# polarshield3_0.net
KiCad netlist of a schematic drawn in EAGLE
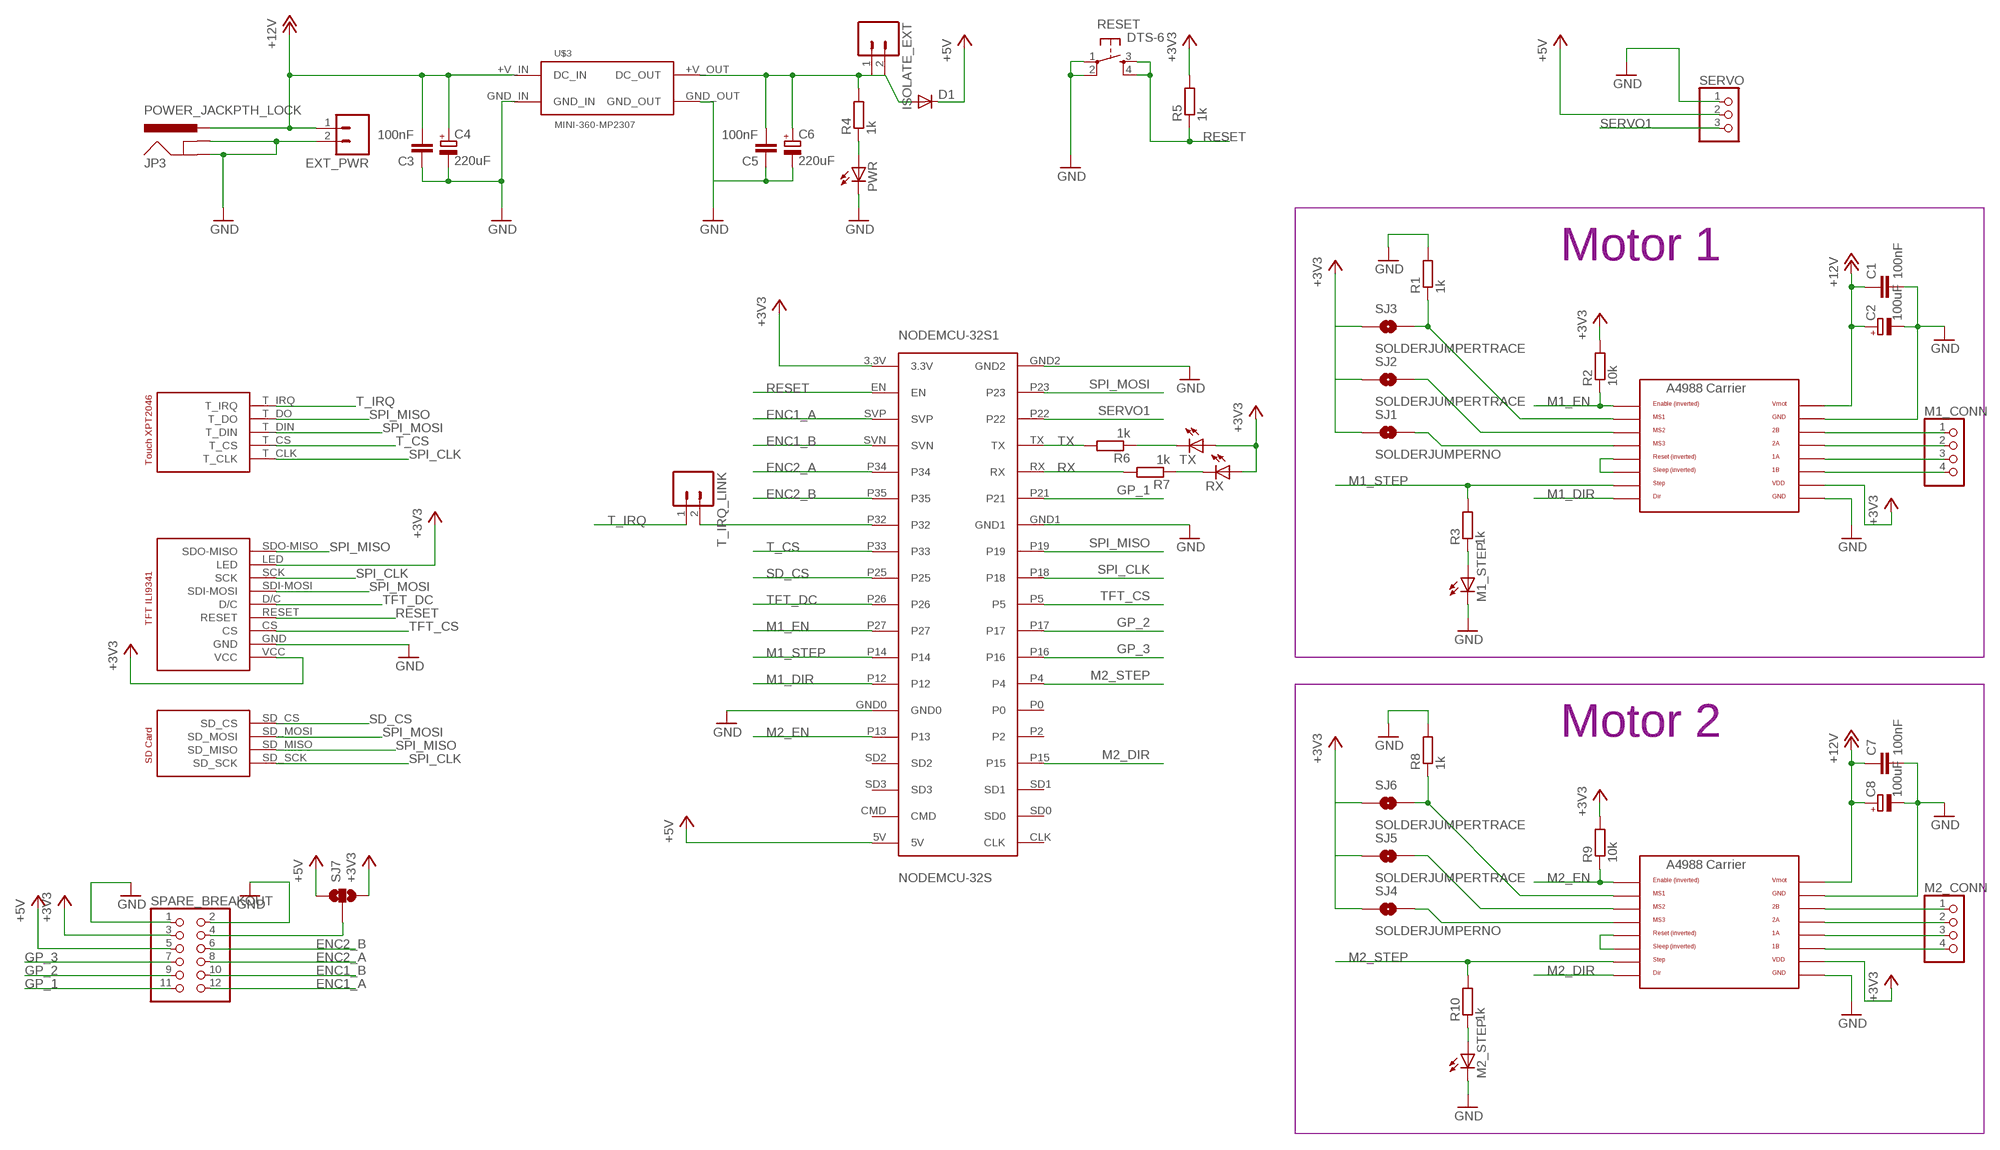
[diagram p0: schematic, sheet 1]

(export (version "E")
  (design (tool "Eeschema 10.0.6"))
  (components
    (comp (ref "C1")
      (value "100nF")
      (footprint "eagle-import:C0805")
      (libsource (lib "eagle-import") (part "C-EUC0805"))
    )
    (comp (ref "C2")
      (value "100uF")
      (footprint "eagle-import:153CLV-0605")
      (libsource (lib "eagle-import") (part "CPOL-EU153CLV-0605"))
    )
    (comp (ref "C3")
      (value "100nF")
      (footprint "eagle-import:C0805")
      (libsource (lib "eagle-import") (part "C-EUC0805"))
    )
    (comp (ref "C4")
      (value "220uF")
      (footprint "eagle-import:153CLV-0605")
      (libsource (lib "eagle-import") (part "CPOL-EU153CLV-0605"))
    )
    (comp (ref "C5")
      (value "100nF")
      (footprint "eagle-import:C0805")
      (libsource (lib "eagle-import") (part "C-EUC0805"))
    )
    (comp (ref "C6")
      (value "220uF")
      (footprint "eagle-import:153CLV-0605")
      (libsource (lib "eagle-import") (part "CPOL-EU153CLV-0605"))
    )
    (comp (ref "C7")
      (value "100nF")
      (footprint "eagle-import:C0805")
      (libsource (lib "eagle-import") (part "C-EUC0805"))
    )
    (comp (ref "C8")
      (value "100uF")
      (footprint "eagle-import:153CLV-0605")
      (libsource (lib "eagle-import") (part "CPOL-EU153CLV-0605"))
    )
    (comp (ref "D1")
      (value "DIODE-DO214BA")
      (footprint "eagle-import:DO214BA")
      (libsource (lib "eagle-import") (part "DIODE-DO214BA"))
    )
    (comp (ref "EXT_PWR")
      (value "M02PTH")
      (footprint "eagle-import:1X02")
      (libsource (lib "eagle-import") (part "M02PTH"))
    )
    (comp (ref "ISOLATE_EXT")
      (value "M02PTH")
      (footprint "eagle-import:1X02")
      (libsource (lib "eagle-import") (part "M02PTH"))
    )
    (comp (ref "JP3")
      (value "POWER_JACKPTH_LOCK")
      (footprint "eagle-import:POWER_JACK_PTH_LOCK")
      (libsource (lib "eagle-import") (part "POWER_JACKPTH_LOCK"))
    )
    (comp (ref "M1_CONN")
      (value "PINHD-1X4/90")
      (footprint "eagle-import:1X04_90")
      (libsource (lib "eagle-import") (part "PINHD-1X4/90"))
    )
    (comp (ref "M1_STEP")
      (value "LEDCHIPLED_0805")
      (footprint "eagle-import:CHIPLED_0805")
      (libsource (lib "eagle-import") (part "LEDCHIPLED_0805"))
    )
    (comp (ref "M2_CONN")
      (value "PINHD-1X4/90")
      (footprint "eagle-import:1X04_90")
      (libsource (lib "eagle-import") (part "PINHD-1X4/90"))
    )
    (comp (ref "M2_STEP")
      (value "LEDCHIPLED_0805")
      (footprint "eagle-import:CHIPLED_0805")
      (libsource (lib "eagle-import") (part "LEDCHIPLED_0805"))
    )
    (comp (ref "MOTOR_1")
      (value "A4988BREAKOUT")
      (footprint "eagle-import:A4988BREAKOUT")
      (libsource (lib "eagle-import") (part "A4988BREAKOUT"))
    )
    (comp (ref "MOTOR_2")
      (value "A4988BREAKOUT")
      (footprint "eagle-import:A4988BREAKOUT")
      (libsource (lib "eagle-import") (part "A4988BREAKOUT"))
    )
    (comp (ref "NODEMCU-32S1")
      (value "NODEMCU-32S")
      (footprint "eagle-import:NODEMCU-32S")
      (libsource (lib "eagle-import") (part "NODEMCU-32S"))
    )
    (comp (ref "PWR")
      (value "LEDCHIPLED_0805")
      (footprint "eagle-import:CHIPLED_0805")
      (libsource (lib "eagle-import") (part "LEDCHIPLED_0805"))
    )
    (comp (ref "R1")
      (value "1k")
      (footprint "eagle-import:M0805")
      (libsource (lib "eagle-import") (part "R-EU_M0805"))
    )
    (comp (ref "R2")
      (value "10k")
      (footprint "eagle-import:M0805")
      (libsource (lib "eagle-import") (part "R-EU_M0805"))
    )
    (comp (ref "R3")
      (value "1k")
      (footprint "eagle-import:M0805")
      (libsource (lib "eagle-import") (part "R-EU_M0805"))
    )
    (comp (ref "R4")
      (value "1k")
      (footprint "eagle-import:M0805")
      (libsource (lib "eagle-import") (part "R-EU_M0805"))
    )
    (comp (ref "R5")
      (value "1k")
      (footprint "eagle-import:M0805")
      (libsource (lib "eagle-import") (part "R-EU_M0805"))
    )
    (comp (ref "R6")
      (value "1k")
      (footprint "eagle-import:M0805")
      (libsource (lib "eagle-import") (part "R-EU_M0805"))
    )
    (comp (ref "R7")
      (value "1k")
      (footprint "eagle-import:M0805")
      (libsource (lib "eagle-import") (part "R-EU_M0805"))
    )
    (comp (ref "R8")
      (value "1k")
      (footprint "eagle-import:M0805")
      (libsource (lib "eagle-import") (part "R-EU_M0805"))
    )
    (comp (ref "R9")
      (value "10k")
      (footprint "eagle-import:M0805")
      (libsource (lib "eagle-import") (part "R-EU_M0805"))
    )
    (comp (ref "R10")
      (value "1k")
      (footprint "eagle-import:M0805")
      (libsource (lib "eagle-import") (part "R-EU_M0805"))
    )
    (comp (ref "RESET")
      (value "DTS-6")
      (footprint "eagle-import:DTS-6")
      (libsource (lib "eagle-import") (part "DTS-6"))
    )
    (comp (ref "RX")
      (value "LEDCHIPLED_0805")
      (footprint "eagle-import:CHIPLED_0805")
      (libsource (lib "eagle-import") (part "LEDCHIPLED_0805"))
    )
    (comp (ref "SERVO")
      (value "PINHD-1X3/90")
      (footprint "eagle-import:1X03_90")
      (libsource (lib "eagle-import") (part "PINHD-1X3/90"))
    )
    (comp (ref "SJ1")
      (value "SOLDERJUMPERNO")
      (footprint "eagle-import:SJ_2S-NO")
      (libsource (lib "eagle-import") (part "SOLDERJUMPERNO"))
    )
    (comp (ref "SJ2")
      (value "SOLDERJUMPERTRACE")
      (footprint "eagle-import:SJ_2S-TRACE")
      (libsource (lib "eagle-import") (part "SOLDERJUMPERTRACE"))
    )
    (comp (ref "SJ3")
      (value "SOLDERJUMPERTRACE")
      (footprint "eagle-import:SJ_2S-TRACE")
      (libsource (lib "eagle-import") (part "SOLDERJUMPERTRACE"))
    )
    (comp (ref "SJ4")
      (value "SOLDERJUMPERNO")
      (footprint "eagle-import:SJ_2S-NO")
      (libsource (lib "eagle-import") (part "SOLDERJUMPERNO"))
    )
    (comp (ref "SJ5")
      (value "SOLDERJUMPERTRACE")
      (footprint "eagle-import:SJ_2S-TRACE")
      (libsource (lib "eagle-import") (part "SOLDERJUMPERTRACE"))
    )
    (comp (ref "SJ6")
      (value "SOLDERJUMPERTRACE")
      (footprint "eagle-import:SJ_2S-TRACE")
      (libsource (lib "eagle-import") (part "SOLDERJUMPERTRACE"))
    )
    (comp (ref "SJ7")
      (value "SOLDERJUMPER_2WAYPASTE1&2")
      (footprint "eagle-import:SJ_3_PASTE1&2")
      (libsource (lib "eagle-import") (part "SOLDERJUMPER_2WAYPASTE1&2"))
    )
    (comp (ref "SPARE_BREAKOUT")
      (value "PINHD-2X6")
      (footprint "eagle-import:2X06")
      (libsource (lib "eagle-import") (part "PINHD-2X6"))
    )
    (comp (ref "TX")
      (value "LEDCHIPLED_0805")
      (footprint "eagle-import:CHIPLED_0805")
      (libsource (lib "eagle-import") (part "LEDCHIPLED_0805"))
    )
    (comp (ref "T_IRQ_LINK")
      (value "M02PTH")
      (footprint "eagle-import:1X02")
      (libsource (lib "eagle-import") (part "M02PTH"))
    )
    (comp (ref "U$2")
      (value "2.4_TFT_SPI_TOUCH_SD")
      (footprint "eagle-import:2.4_TFT_SPI_TOUCH_SD")
      (libsource (lib "eagle-import") (part "2.4_TFT_SPI_TOUCH_SD"))
    )
    (comp (ref "U$3")
      (value "MINI-360-MP2307")
      (footprint "eagle-import:MINI-360-MP2307")
      (libsource (lib "eagle-import") (part "MINI-360-MP2307"))
    )
  )
  (nets
    (net (code "1") (name "+3V3") (class "Default")
      (node (ref "MOTOR_1") (pin "VDD") (pinfunction "VDD_VDD") (pintype "power_in"))
      (node (ref "MOTOR_2") (pin "VDD") (pinfunction "VDD_VDD") (pintype "power_in"))
      (node (ref "NODEMCU-32S1") (pin "3.3V") (pinfunction "3.3V_3.3V") (pintype "bidirectional"))
      (node (ref "R2") (pin "2") (pinfunction "2_2") (pintype "passive"))
      (node (ref "R5") (pin "2") (pinfunction "2_2") (pintype "passive"))
      (node (ref "R9") (pin "2") (pinfunction "2_2") (pintype "passive"))
      (node (ref "RX") (pin "A") (pinfunction "A_A") (pintype "passive"))
      (node (ref "SJ1") (pin "1") (pinfunction "1_1") (pintype "passive"))
      (node (ref "SJ2") (pin "1") (pinfunction "1_1") (pintype "passive"))
      (node (ref "SJ3") (pin "1") (pinfunction "1_1") (pintype "passive"))
      (node (ref "SJ4") (pin "1") (pinfunction "1_1") (pintype "passive"))
      (node (ref "SJ5") (pin "1") (pinfunction "1_1") (pintype "passive"))
      (node (ref "SJ6") (pin "1") (pinfunction "1_1") (pintype "passive"))
      (node (ref "SJ7") (pin "3") (pinfunction "3_3") (pintype "passive"))
      (node (ref "SPARE_BREAKOUT") (pin "3") (pinfunction "3_3") (pintype "passive"))
      (node (ref "TX") (pin "A") (pinfunction "A_A") (pintype "passive"))
      (node (ref "U$2") (pin "LED") (pinfunction "LED_LED") (pintype "bidirectional"))
      (node (ref "U$2") (pin "VCC") (pinfunction "VCC_VCC") (pintype "bidirectional"))
    )
    (net (code "2") (name "+5V") (class "Default")
      (node (ref "D1") (pin "C") (pinfunction "C_C") (pintype "passive"))
      (node (ref "NODEMCU-32S1") (pin "5V") (pinfunction "5V_5V") (pintype "bidirectional"))
      (node (ref "SERVO") (pin "2") (pinfunction "2_2") (pintype "passive"))
      (node (ref "SJ7") (pin "1") (pinfunction "1_1") (pintype "passive"))
      (node (ref "SPARE_BREAKOUT") (pin "5") (pinfunction "5_5") (pintype "passive"))
    )
    (net (code "3") (name "+12V") (class "Default")
      (node (ref "C1") (pin "1") (pinfunction "1_1") (pintype "passive"))
      (node (ref "C2") (pin "+") (pinfunction "+_+") (pintype "passive"))
      (node (ref "C3") (pin "2") (pinfunction "2_2") (pintype "passive"))
      (node (ref "C4") (pin "+") (pinfunction "+_+") (pintype "passive"))
      (node (ref "C7") (pin "1") (pinfunction "1_1") (pintype "passive"))
      (node (ref "C8") (pin "+") (pinfunction "+_+") (pintype "passive"))
      (node (ref "EXT_PWR") (pin "1") (pinfunction "1_1") (pintype "passive"))
      (node (ref "JP3") (pin "PWR") (pinfunction "PWR_PWR") (pintype "bidirectional"))
      (node (ref "MOTOR_1") (pin "VMOT") (pinfunction "VMOT_VMOT") (pintype "power_in"))
      (node (ref "MOTOR_2") (pin "VMOT") (pinfunction "VMOT_VMOT") (pintype "power_in"))
      (node (ref "U$3") (pin "+V_IN") (pinfunction "DC_IN_+V_IN") (pintype "bidirectional"))
    )
    (net (code "4") (name "/ENC1_A") (class "Default")
      (node (ref "NODEMCU-32S1") (pin "SVP") (pinfunction "SVP_SVP") (pintype "bidirectional"))
      (node (ref "SPARE_BREAKOUT") (pin "12") (pinfunction "12_12") (pintype "passive"))
    )
    (net (code "5") (name "/ENC1_B") (class "Default")
      (node (ref "NODEMCU-32S1") (pin "SVN") (pinfunction "SVN_SVN") (pintype "bidirectional"))
      (node (ref "SPARE_BREAKOUT") (pin "10") (pinfunction "10_10") (pintype "passive"))
    )
    (net (code "6") (name "/ENC2_A") (class "Default")
      (node (ref "NODEMCU-32S1") (pin "P34") (pinfunction "P34_P34") (pintype "bidirectional"))
      (node (ref "SPARE_BREAKOUT") (pin "8") (pinfunction "8_8") (pintype "passive"))
    )
    (net (code "7") (name "/ENC2_B") (class "Default")
      (node (ref "NODEMCU-32S1") (pin "P35") (pinfunction "P35_P35") (pintype "bidirectional"))
      (node (ref "SPARE_BREAKOUT") (pin "6") (pinfunction "6_6") (pintype "passive"))
    )
    (net (code "8") (name "/GP_1") (class "Default")
      (node (ref "NODEMCU-32S1") (pin "P21") (pinfunction "P21_P21") (pintype "bidirectional"))
      (node (ref "SPARE_BREAKOUT") (pin "11") (pinfunction "11_11") (pintype "passive"))
    )
    (net (code "9") (name "/GP_2") (class "Default")
      (node (ref "NODEMCU-32S1") (pin "P17") (pinfunction "P17_P17") (pintype "bidirectional"))
      (node (ref "SPARE_BREAKOUT") (pin "9") (pinfunction "9_9") (pintype "passive"))
    )
    (net (code "10") (name "/GP_3") (class "Default")
      (node (ref "NODEMCU-32S1") (pin "P16") (pinfunction "P16_P16") (pintype "bidirectional"))
      (node (ref "SPARE_BREAKOUT") (pin "7") (pinfunction "7_7") (pintype "passive"))
    )
    (net (code "11") (name "/M1_DIR") (class "Default")
      (node (ref "MOTOR_1") (pin "DIR") (pinfunction "DIR_DIR") (pintype "input"))
      (node (ref "NODEMCU-32S1") (pin "P12") (pinfunction "P12_P12") (pintype "bidirectional"))
    )
    (net (code "12") (name "/M1_EN") (class "Default")
      (node (ref "MOTOR_1") (pin "EN") (pinfunction "EN_EN") (pintype "input"))
      (node (ref "NODEMCU-32S1") (pin "P27") (pinfunction "P27_P27") (pintype "bidirectional"))
      (node (ref "R2") (pin "1") (pinfunction "1_1") (pintype "passive"))
    )
    (net (code "13") (name "/M1_STEP") (class "Default")
      (node (ref "MOTOR_1") (pin "STEP") (pinfunction "STEP_STEP") (pintype "input"))
      (node (ref "NODEMCU-32S1") (pin "P14") (pinfunction "P14_P14") (pintype "bidirectional"))
      (node (ref "R3") (pin "2") (pinfunction "2_2") (pintype "passive"))
    )
    (net (code "14") (name "/M2_DIR") (class "Default")
      (node (ref "MOTOR_2") (pin "DIR") (pinfunction "DIR_DIR") (pintype "input"))
      (node (ref "NODEMCU-32S1") (pin "P15") (pinfunction "P15_P15") (pintype "bidirectional"))
    )
    (net (code "15") (name "/M2_EN") (class "Default")
      (node (ref "MOTOR_2") (pin "EN") (pinfunction "EN_EN") (pintype "input"))
      (node (ref "NODEMCU-32S1") (pin "P13") (pinfunction "P13_P13") (pintype "bidirectional"))
      (node (ref "R9") (pin "1") (pinfunction "1_1") (pintype "passive"))
    )
    (net (code "16") (name "/M2_STEP") (class "Default")
      (node (ref "MOTOR_2") (pin "STEP") (pinfunction "STEP_STEP") (pintype "input"))
      (node (ref "NODEMCU-32S1") (pin "P4") (pinfunction "P4_P4") (pintype "bidirectional"))
      (node (ref "R10") (pin "2") (pinfunction "2_2") (pintype "passive"))
    )
    (net (code "17") (name "/RESET") (class "Default")
      (node (ref "NODEMCU-32S1") (pin "EN") (pinfunction "EN_EN") (pintype "bidirectional"))
      (node (ref "R5") (pin "1") (pinfunction "1_1") (pintype "passive"))
      (node (ref "RESET") (pin "3") (pinfunction "3_3") (pintype "passive"))
      (node (ref "RESET") (pin "4") (pinfunction "4_4") (pintype "passive"))
      (node (ref "U$2") (pin "RESET") (pinfunction "RESET_RESET") (pintype "bidirectional"))
    )
    (net (code "18") (name "/RX") (class "Default")
      (node (ref "NODEMCU-32S1") (pin "RX") (pinfunction "RX_RX") (pintype "bidirectional"))
      (node (ref "R7") (pin "2") (pinfunction "2_2") (pintype "passive"))
    )
    (net (code "19") (name "/SD_CS") (class "Default")
      (node (ref "NODEMCU-32S1") (pin "P25") (pinfunction "P25_P25") (pintype "bidirectional"))
      (node (ref "U$2") (pin "SD_CS") (pinfunction "SD_CS_SD_CS") (pintype "bidirectional"))
    )
    (net (code "20") (name "/SERVO1") (class "Default")
      (node (ref "NODEMCU-32S1") (pin "P22") (pinfunction "P22_P22") (pintype "bidirectional"))
      (node (ref "SERVO") (pin "3") (pinfunction "3_3") (pintype "passive"))
    )
    (net (code "21") (name "/SPI_CLK") (class "Default")
      (node (ref "NODEMCU-32S1") (pin "P18") (pinfunction "P18_P18") (pintype "bidirectional"))
      (node (ref "U$2") (pin "SCK") (pinfunction "SCK_SCK") (pintype "bidirectional"))
      (node (ref "U$2") (pin "SD_SCK") (pinfunction "SD_SCK_SD_SCK") (pintype "bidirectional"))
      (node (ref "U$2") (pin "T_CLK") (pinfunction "T_CLK_T_CLK") (pintype "input"))
    )
    (net (code "22") (name "/SPI_MISO") (class "Default")
      (node (ref "NODEMCU-32S1") (pin "P19") (pinfunction "P19_P19") (pintype "bidirectional"))
      (node (ref "U$2") (pin "SDO-MISO") (pinfunction "SDO-MISO_SDO-MISO") (pintype "bidirectional"))
      (node (ref "U$2") (pin "SD_MISO") (pinfunction "SD_MISO_SD_MISO") (pintype "bidirectional"))
      (node (ref "U$2") (pin "T_DO") (pinfunction "T_DO_T_DO") (pintype "output"))
    )
    (net (code "23") (name "/SPI_MOSI") (class "Default")
      (node (ref "NODEMCU-32S1") (pin "P23") (pinfunction "P23_P23") (pintype "bidirectional"))
      (node (ref "U$2") (pin "SDI-MOSI") (pinfunction "SDI-MOSI_SDI-MOSI") (pintype "bidirectional"))
      (node (ref "U$2") (pin "SD_MOSI") (pinfunction "SD_MOSI_SD_MOSI") (pintype "bidirectional"))
      (node (ref "U$2") (pin "T_DIN") (pinfunction "T_DIN_T_DIN") (pintype "input"))
    )
    (net (code "24") (name "/TFT_CS") (class "Default")
      (node (ref "NODEMCU-32S1") (pin "P5") (pinfunction "P5_P5") (pintype "bidirectional"))
      (node (ref "U$2") (pin "CS") (pinfunction "CS_CS") (pintype "bidirectional"))
    )
    (net (code "25") (name "/TFT_DC") (class "Default")
      (node (ref "NODEMCU-32S1") (pin "P26") (pinfunction "P26_P26") (pintype "bidirectional"))
      (node (ref "U$2") (pin "D/C") (pinfunction "D/C_D/C") (pintype "bidirectional"))
    )
    (net (code "26") (name "/TX") (class "Default")
      (node (ref "NODEMCU-32S1") (pin "TX") (pinfunction "TX_TX") (pintype "bidirectional"))
      (node (ref "R6") (pin "2") (pinfunction "2_2") (pintype "passive"))
    )
    (net (code "27") (name "/T_CS") (class "Default")
      (node (ref "NODEMCU-32S1") (pin "P33") (pinfunction "P33_P33") (pintype "bidirectional"))
      (node (ref "U$2") (pin "T_CS") (pinfunction "T_CS_T_CS") (pintype "output"))
    )
    (net (code "28") (name "/T_IRQ") (class "Default")
      (node (ref "T_IRQ_LINK") (pin "1") (pinfunction "1_1") (pintype "passive"))
      (node (ref "U$2") (pin "T_IRQ") (pinfunction "T_IRQ_T_IRQ") (pintype "output"))
    )
    (net (code "29") (name "GND") (class "Default")
      (node (ref "C1") (pin "2") (pinfunction "2_2") (pintype "passive"))
      (node (ref "C2") (pin "-") (pinfunction "-_-") (pintype "passive"))
      (node (ref "C3") (pin "1") (pinfunction "1_1") (pintype "passive"))
      (node (ref "C4") (pin "-") (pinfunction "-_-") (pintype "passive"))
      (node (ref "C5") (pin "1") (pinfunction "1_1") (pintype "passive"))
      (node (ref "C6") (pin "-") (pinfunction "-_-") (pintype "passive"))
      (node (ref "C7") (pin "2") (pinfunction "2_2") (pintype "passive"))
      (node (ref "C8") (pin "-") (pinfunction "-_-") (pintype "passive"))
      (node (ref "EXT_PWR") (pin "2") (pinfunction "2_2") (pintype "passive"))
      (node (ref "JP3") (pin "GND") (pinfunction "GND_GND") (pintype "bidirectional"))
      (node (ref "JP3") (pin "GNDBREAK") (pinfunction "GNDBREAK_GNDBREAK") (pintype "bidirectional"))
      (node (ref "M1_STEP") (pin "C") (pinfunction "C_C") (pintype "passive"))
      (node (ref "M2_STEP") (pin "C") (pinfunction "C_C") (pintype "passive"))
      (node (ref "MOTOR_1") (pin "GND") (pinfunction "GND_GND") (pintype "power_in"))
      (node (ref "MOTOR_1") (pin "GND@0") (pinfunction "GND_GND@0") (pintype "power_in"))
      (node (ref "MOTOR_2") (pin "GND") (pinfunction "GND_GND") (pintype "power_in"))
      (node (ref "MOTOR_2") (pin "GND@0") (pinfunction "GND_GND@0") (pintype "power_in"))
      (node (ref "NODEMCU-32S1") (pin "GND0") (pinfunction "GND0_GND0") (pintype "bidirectional"))
      (node (ref "NODEMCU-32S1") (pin "GND1") (pinfunction "GND1_GND1") (pintype "bidirectional"))
      (node (ref "NODEMCU-32S1") (pin "GND2") (pinfunction "GND2_GND2") (pintype "bidirectional"))
      (node (ref "PWR") (pin "C") (pinfunction "C_C") (pintype "passive"))
      (node (ref "R1") (pin "2") (pinfunction "2_2") (pintype "passive"))
      (node (ref "R8") (pin "2") (pinfunction "2_2") (pintype "passive"))
      (node (ref "RESET") (pin "1") (pinfunction "1_1") (pintype "passive"))
      (node (ref "RESET") (pin "2") (pinfunction "2_2") (pintype "passive"))
      (node (ref "SERVO") (pin "1") (pinfunction "1_1") (pintype "passive"))
      (node (ref "SPARE_BREAKOUT") (pin "1") (pinfunction "1_1") (pintype "passive"))
      (node (ref "SPARE_BREAKOUT") (pin "2") (pinfunction "2_2") (pintype "passive"))
      (node (ref "U$2") (pin "GND") (pinfunction "GND_GND") (pintype "bidirectional"))
      (node (ref "U$3") (pin "GND_IN") (pinfunction "GND_IN_GND_IN") (pintype "bidirectional"))
      (node (ref "U$3") (pin "GND_OUT") (pinfunction "GND_OUT_GND_OUT") (pintype "bidirectional"))
    )
    (net (code "30") (name "Net-(M1_CONN-Pad1)") (class "Default")
      (node (ref "M1_CONN") (pin "1") (pinfunction "1_1") (pintype "passive"))
      (node (ref "MOTOR_1") (pin "2B") (pinfunction "2B_2B") (pintype "output"))
    )
    (net (code "31") (name "Net-(M1_CONN-Pad2)") (class "Default")
      (node (ref "M1_CONN") (pin "2") (pinfunction "2_2") (pintype "passive"))
      (node (ref "MOTOR_1") (pin "2A") (pinfunction "2A_2A") (pintype "output"))
    )
    (net (code "32") (name "Net-(M1_CONN-Pad3)") (class "Default")
      (node (ref "M1_CONN") (pin "3") (pinfunction "3_3") (pintype "passive"))
      (node (ref "MOTOR_1") (pin "1A") (pinfunction "1A_1A") (pintype "output"))
    )
    (net (code "33") (name "Net-(M1_CONN-Pad4)") (class "Default")
      (node (ref "M1_CONN") (pin "4") (pinfunction "4_4") (pintype "passive"))
      (node (ref "MOTOR_1") (pin "1B") (pinfunction "1B_1B") (pintype "output"))
    )
    (net (code "34") (name "Net-(M1_STEP-PadA)") (class "Default")
      (node (ref "M1_STEP") (pin "A") (pinfunction "A_A") (pintype "passive"))
      (node (ref "R3") (pin "1") (pinfunction "1_1") (pintype "passive"))
    )
    (net (code "35") (name "Net-(M2_CONN-Pad1)") (class "Default")
      (node (ref "M2_CONN") (pin "1") (pinfunction "1_1") (pintype "passive"))
      (node (ref "MOTOR_2") (pin "2B") (pinfunction "2B_2B") (pintype "output"))
    )
    (net (code "36") (name "Net-(M2_CONN-Pad2)") (class "Default")
      (node (ref "M2_CONN") (pin "2") (pinfunction "2_2") (pintype "passive"))
      (node (ref "MOTOR_2") (pin "2A") (pinfunction "2A_2A") (pintype "output"))
    )
    (net (code "37") (name "Net-(M2_CONN-Pad3)") (class "Default")
      (node (ref "M2_CONN") (pin "3") (pinfunction "3_3") (pintype "passive"))
      (node (ref "MOTOR_2") (pin "1A") (pinfunction "1A_1A") (pintype "output"))
    )
    (net (code "38") (name "Net-(M2_CONN-Pad4)") (class "Default")
      (node (ref "M2_CONN") (pin "4") (pinfunction "4_4") (pintype "passive"))
      (node (ref "MOTOR_2") (pin "1B") (pinfunction "1B_1B") (pintype "output"))
    )
    (net (code "39") (name "Net-(M2_STEP-PadA)") (class "Default")
      (node (ref "M2_STEP") (pin "A") (pinfunction "A_A") (pintype "passive"))
      (node (ref "R10") (pin "1") (pinfunction "1_1") (pintype "passive"))
    )
    (net (code "40") (name "Net-(MOTOR_1-PadMS1)") (class "Default")
      (node (ref "MOTOR_1") (pin "MS1") (pinfunction "MS1_MS1") (pintype "input"))
      (node (ref "R1") (pin "1") (pinfunction "1_1") (pintype "passive"))
      (node (ref "SJ3") (pin "2") (pinfunction "2_2") (pintype "passive"))
    )
    (net (code "41") (name "Net-(MOTOR_1-PadMS2)") (class "Default")
      (node (ref "MOTOR_1") (pin "MS2") (pinfunction "MS2_MS2") (pintype "input"))
      (node (ref "SJ2") (pin "2") (pinfunction "2_2") (pintype "passive"))
    )
    (net (code "42") (name "Net-(MOTOR_1-PadMS3)") (class "Default")
      (node (ref "MOTOR_1") (pin "MS3") (pinfunction "MS3_MS3") (pintype "input"))
      (node (ref "SJ1") (pin "2") (pinfunction "2_2") (pintype "passive"))
    )
    (net (code "43") (name "Net-(MOTOR_1-SLEEP)") (class "Default")
      (node (ref "MOTOR_1") (pin "RST") (pinfunction "RST_RST") (pintype "input"))
      (node (ref "MOTOR_1") (pin "SLP") (pinfunction "SLEEP_SLP") (pintype "input"))
    )
    (net (code "44") (name "Net-(MOTOR_2-PadMS1)") (class "Default")
      (node (ref "MOTOR_2") (pin "MS1") (pinfunction "MS1_MS1") (pintype "input"))
      (node (ref "R8") (pin "1") (pinfunction "1_1") (pintype "passive"))
      (node (ref "SJ6") (pin "2") (pinfunction "2_2") (pintype "passive"))
    )
    (net (code "45") (name "Net-(MOTOR_2-PadMS2)") (class "Default")
      (node (ref "MOTOR_2") (pin "MS2") (pinfunction "MS2_MS2") (pintype "input"))
      (node (ref "SJ5") (pin "2") (pinfunction "2_2") (pintype "passive"))
    )
    (net (code "46") (name "Net-(MOTOR_2-PadMS3)") (class "Default")
      (node (ref "MOTOR_2") (pin "MS3") (pinfunction "MS3_MS3") (pintype "input"))
      (node (ref "SJ4") (pin "2") (pinfunction "2_2") (pintype "passive"))
    )
    (net (code "47") (name "Net-(MOTOR_2-SLEEP)") (class "Default")
      (node (ref "MOTOR_2") (pin "RST") (pinfunction "RST_RST") (pintype "input"))
      (node (ref "MOTOR_2") (pin "SLP") (pinfunction "SLEEP_SLP") (pintype "input"))
    )
    (net (code "48") (name "Net-(NODEMCU-32S1-PadP32)") (class "Default")
      (node (ref "NODEMCU-32S1") (pin "P32") (pinfunction "P32_P32") (pintype "bidirectional"))
      (node (ref "T_IRQ_LINK") (pin "2") (pinfunction "2_2") (pintype "passive"))
    )
    (net (code "49") (name "Net-(PWR-PadA)") (class "Default")
      (node (ref "PWR") (pin "A") (pinfunction "A_A") (pintype "passive"))
      (node (ref "R4") (pin "1") (pinfunction "1_1") (pintype "passive"))
    )
    (net (code "50") (name "Net-(R6-Pad1)") (class "Default")
      (node (ref "R6") (pin "1") (pinfunction "1_1") (pintype "passive"))
      (node (ref "TX") (pin "C") (pinfunction "C_C") (pintype "passive"))
    )
    (net (code "51") (name "Net-(R7-Pad1)") (class "Default")
      (node (ref "R7") (pin "1") (pinfunction "1_1") (pintype "passive"))
      (node (ref "RX") (pin "C") (pinfunction "C_C") (pintype "passive"))
    )
    (net (code "52") (name "Net-(SJ7-Pad2)") (class "Default")
      (node (ref "SJ7") (pin "2") (pinfunction "2_2") (pintype "passive"))
      (node (ref "SPARE_BREAKOUT") (pin "4") (pinfunction "4_4") (pintype "passive"))
    )
    (net (code "53") (name "Net-(U$3-DC_OUT)") (class "Default")
      (node (ref "C5") (pin "2") (pinfunction "2_2") (pintype "passive"))
      (node (ref "C6") (pin "+") (pinfunction "+_+") (pintype "passive"))
      (node (ref "D1") (pin "A") (pinfunction "A_A") (pintype "passive"))
      (node (ref "ISOLATE_EXT") (pin "1") (pinfunction "1_1") (pintype "passive"))
      (node (ref "ISOLATE_EXT") (pin "2") (pinfunction "2_2") (pintype "passive"))
      (node (ref "R4") (pin "2") (pinfunction "2_2") (pintype "passive"))
      (node (ref "U$3") (pin "+V_OUT") (pinfunction "DC_OUT_+V_OUT") (pintype "bidirectional"))
    )
    (net (code "54") (name "unconnected-(NODEMCU-32S1-PadCLK)") (class "Default")
      (node (ref "NODEMCU-32S1") (pin "CLK") (pinfunction "CLK_CLK") (pintype "bidirectional"))
    )
    (net (code "55") (name "unconnected-(NODEMCU-32S1-PadCMD)") (class "Default")
      (node (ref "NODEMCU-32S1") (pin "CMD") (pinfunction "CMD_CMD") (pintype "bidirectional"))
    )
    (net (code "56") (name "unconnected-(NODEMCU-32S1-PadP0)") (class "Default")
      (node (ref "NODEMCU-32S1") (pin "P0") (pinfunction "P0_P0") (pintype "bidirectional"))
    )
    (net (code "57") (name "unconnected-(NODEMCU-32S1-PadP2)") (class "Default")
      (node (ref "NODEMCU-32S1") (pin "P2") (pinfunction "P2_P2") (pintype "bidirectional"))
    )
    (net (code "58") (name "unconnected-(NODEMCU-32S1-PadSD0)") (class "Default")
      (node (ref "NODEMCU-32S1") (pin "SD0") (pinfunction "SD0_SD0") (pintype "bidirectional"))
    )
    (net (code "59") (name "unconnected-(NODEMCU-32S1-PadSD1)") (class "Default")
      (node (ref "NODEMCU-32S1") (pin "SD1") (pinfunction "SD1_SD1") (pintype "bidirectional"))
    )
    (net (code "60") (name "unconnected-(NODEMCU-32S1-PadSD2)") (class "Default")
      (node (ref "NODEMCU-32S1") (pin "SD2") (pinfunction "SD2_SD2") (pintype "bidirectional"))
    )
    (net (code "61") (name "unconnected-(NODEMCU-32S1-PadSD3)") (class "Default")
      (node (ref "NODEMCU-32S1") (pin "SD3") (pinfunction "SD3_SD3") (pintype "bidirectional"))
    )
  )
)
